# E-P-020-R1_0.net
KiCad netlist of a schematic drawn in EAGLE
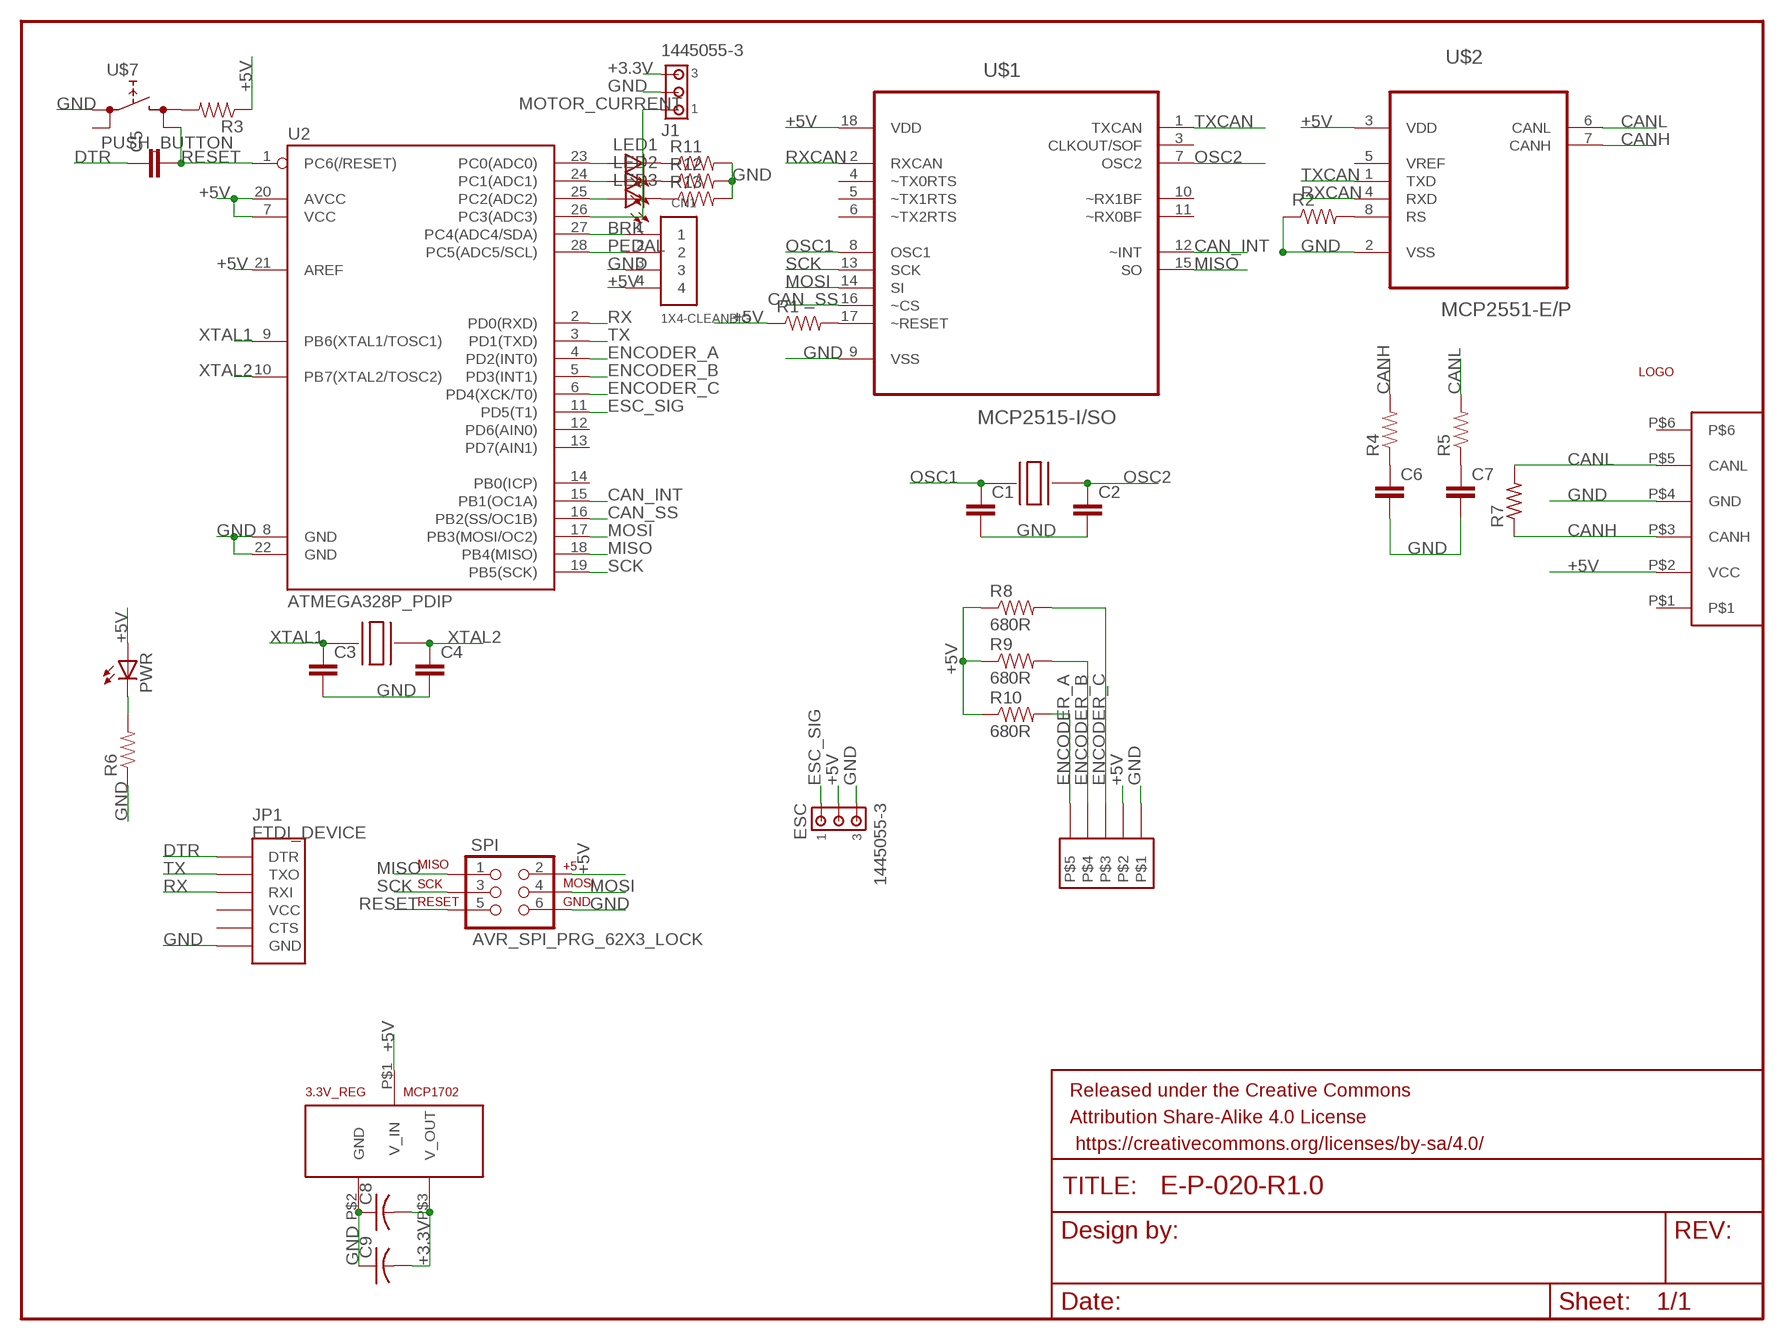
[diagram p0: schematic, sheet 1]

(export (version "E")
  (design (tool "Eeschema 10.0.6"))
  (components
    (comp (ref "3.3V_REG")
      (value "MCP1702")
      (footprint "eagle-import:SOT-23A")
      (libsource (lib "eagle-import") (part "MCP1702"))
    )
    (comp (ref "C1")
      (value "CAP0805")
      (footprint "eagle-import:0805")
      (libsource (lib "eagle-import") (part "CAP0805"))
    )
    (comp (ref "C2")
      (value "CAP0805")
      (footprint "eagle-import:0805")
      (libsource (lib "eagle-import") (part "CAP0805"))
    )
    (comp (ref "C3")
      (value "CAP0805")
      (footprint "eagle-import:0805")
      (libsource (lib "eagle-import") (part "CAP0805"))
    )
    (comp (ref "C4")
      (value "CAP0805")
      (footprint "eagle-import:0805")
      (libsource (lib "eagle-import") (part "CAP0805"))
    )
    (comp (ref "C5")
      (value "CAP0805")
      (footprint "eagle-import:0805")
      (libsource (lib "eagle-import") (part "CAP0805"))
    )
    (comp (ref "C6")
      (value "CAP0805")
      (footprint "eagle-import:0805")
      (libsource (lib "eagle-import") (part "CAP0805"))
    )
    (comp (ref "C7")
      (value "CAP0805")
      (footprint "eagle-import:0805")
      (libsource (lib "eagle-import") (part "CAP0805"))
    )
    (comp (ref "C8")
      (value "C-USC0805")
      (footprint "eagle-import:C0805")
      (libsource (lib "eagle-import") (part "C-USC0805"))
    )
    (comp (ref "C9")
      (value "C-USC0805")
      (footprint "eagle-import:C0805")
      (libsource (lib "eagle-import") (part "C-USC0805"))
    )
    (comp (ref "CAN-BUS")
      (value "CAN_6P6C")
      (footprint "eagle-import:CAN_6P6C")
      (libsource (lib "eagle-import") (part "CAN_6P6C"))
    )
    (comp (ref "CN1")
      (value "1X4-CLEANBIG")
      (footprint "eagle-import:1X04-CLEANBIG")
      (libsource (lib "eagle-import") (part "1X4-CLEANBIG"))
    )
    (comp (ref "ENCODER")
      (value "5_PIN_MICRO_MATE_N_LOCK")
      (footprint "eagle-import:5_PIN_MICRO_MATE_N_LOCK")
      (libsource (lib "eagle-import") (part "5_PIN_MICRO_MATE_N_LOCK"))
    )
    (comp (ref "ESC")
      (value "1445055-3")
      (footprint "eagle-import:1445055-3")
      (libsource (lib "eagle-import") (part "1445055-3"))
    )
    (comp (ref "FRAME1")
      (value "FRAME-LETTERNO_PACKAGE")
      (footprint "eagle-import:DUMMY")
      (fields (field (name "DESIGNER") "Nobody"))
      (libsource (lib "eagle-import") (part "FRAME-LETTERNO_PACKAGE"))
    )
    (comp (ref "J1")
      (value "1445055-3")
      (footprint "eagle-import:1445055-3")
      (libsource (lib "eagle-import") (part "1445055-3"))
    )
    (comp (ref "JP1")
      (value "FTDI_DEVICE")
      (footprint "eagle-import:FTDI_DEVICE_SIDE")
      (libsource (lib "eagle-import") (part "FTDI_DEVICE"))
    )
    (comp (ref "LED1")
      (value "LEDSMT1206")
      (footprint "eagle-import:1206")
      (libsource (lib "eagle-import") (part "adafruit_LEDSMT1206"))
    )
    (comp (ref "LED2")
      (value "LEDSMT1206")
      (footprint "eagle-import:1206")
      (libsource (lib "eagle-import") (part "adafruit_LEDSMT1206"))
    )
    (comp (ref "LED3")
      (value "LEDSMT1206")
      (footprint "eagle-import:1206")
      (libsource (lib "eagle-import") (part "adafruit_LEDSMT1206"))
    )
    (comp (ref "PWR")
      (value "LEDCHIPLED_1206")
      (footprint "eagle-import:CHIPLED_1206")
      (libsource (lib "eagle-import") (part "LEDCHIPLED_1206"))
    )
    (comp (ref "R1")
      (value "RESISTOR0805-RES")
      (footprint "eagle-import:0805")
      (libsource (lib "eagle-import") (part "SparkFun-Passives_RESISTOR0805-RES"))
    )
    (comp (ref "R2")
      (value "RESISTOR0805-RES")
      (footprint "eagle-import:0805")
      (libsource (lib "eagle-import") (part "SparkFun-Passives_RESISTOR0805-RES"))
    )
    (comp (ref "R3")
      (value "RESISTOR0805-RES")
      (footprint "eagle-import:0805")
      (libsource (lib "eagle-import") (part "SparkFun-Passives_RESISTOR0805-RES"))
    )
    (comp (ref "R4")
      (value "RESISTOR0805-RES")
      (footprint "eagle-import:0805")
      (libsource (lib "eagle-import") (part "SparkFun-Passives_RESISTOR0805-RES"))
    )
    (comp (ref "R5")
      (value "RESISTOR0805-RES")
      (footprint "eagle-import:0805")
      (libsource (lib "eagle-import") (part "SparkFun-Passives_RESISTOR0805-RES"))
    )
    (comp (ref "R6")
      (value "RESISTOR0805-RES")
      (footprint "eagle-import:0805")
      (libsource (lib "eagle-import") (part "SparkFun-Passives_RESISTOR0805-RES"))
    )
    (comp (ref "R7")
      (value "R-US_M1206")
      (footprint "eagle-import:M1206")
      (libsource (lib "eagle-import") (part "R-US_M1206"))
    )
    (comp (ref "R8")
      (value "680R")
      (footprint "eagle-import:0805")
      (libsource (lib "eagle-import") (part "0.75OHM-1/4W-1%(0805)"))
    )
    (comp (ref "R9")
      (value "680R")
      (footprint "eagle-import:0805")
      (libsource (lib "eagle-import") (part "0.75OHM-1/4W-1%(0805)"))
    )
    (comp (ref "R10")
      (value "680R")
      (footprint "eagle-import:0805")
      (libsource (lib "eagle-import") (part "0.75OHM-1/4W-1%(0805)"))
    )
    (comp (ref "R11")
      (value "RESISTOR0805-RES")
      (footprint "eagle-import:0805")
      (libsource (lib "eagle-import") (part "RESISTOR0805-RES"))
    )
    (comp (ref "R12")
      (value "RESISTOR0805-RES")
      (footprint "eagle-import:0805")
      (libsource (lib "eagle-import") (part "RESISTOR0805-RES"))
    )
    (comp (ref "R13")
      (value "RESISTOR0805-RES")
      (footprint "eagle-import:0805")
      (libsource (lib "eagle-import") (part "RESISTOR0805-RES"))
    )
    (comp (ref "SPI")
      (value "AVR_SPI_PRG_62X3_LOCK")
      (footprint "eagle-import:2X3_LOCK")
      (libsource (lib "eagle-import") (part "AVR_SPI_PRG_62X3_LOCK"))
    )
    (comp (ref "U$1")
      (value "MCP2515-I/SO")
      (footprint "eagle-import:SOIC127P1034X264-18N")
      (libsource (lib "eagle-import") (part "MCP2515-I/SO"))
    )
    (comp (ref "U$2")
      (value "MCP2551-E/P")
      (footprint "eagle-import:DIP254P762X432-8")
      (libsource (lib "eagle-import") (part "MCP2551-E/P"))
    )
    (comp (ref "U$3")
      (value "CRYSTAL")
      (footprint "eagle-import:7A_CRYSTAL")
      (libsource (lib "eagle-import") (part "CRYSTAL"))
    )
    (comp (ref "U$4")
      (value "CRYSTAL")
      (footprint "eagle-import:7A_CRYSTAL")
      (libsource (lib "eagle-import") (part "CRYSTAL"))
    )
    (comp (ref "U$6")
      (value "LOGO")
      (footprint "eagle-import:LOGO")
      (libsource (lib "eagle-import") (part "LOGO"))
    )
    (comp (ref "U$7")
      (value "PUSH_BUTTON")
      (footprint "eagle-import:PUSHBUTTON")
      (libsource (lib "eagle-import") (part "PUSH_BUTTON"))
    )
    (comp (ref "U2")
      (value "ATMEGA328P_PDIP")
      (footprint "eagle-import:DIL28-3")
      (libsource (lib "eagle-import") (part "ATMEGA328P_PDIP"))
    )
  )
  (nets
    (net (code "1") (name "/+3.3V") (class "Default")
      (node (ref "3.3V_REG") (pin "P$3") (pinfunction "V_OUT_P$3") (pintype "bidirectional"))
      (node (ref "C8") (pin "2") (pinfunction "2_2") (pintype "passive"))
      (node (ref "C9") (pin "2") (pinfunction "2_2") (pintype "passive"))
      (node (ref "J1") (pin "3") (pinfunction "3_3") (pintype "passive"))
    )
    (net (code "2") (name "/+5V") (class "Default")
      (node (ref "3.3V_REG") (pin "P$1") (pinfunction "V_IN_P$1") (pintype "bidirectional"))
      (node (ref "CAN-BUS") (pin "P$2") (pinfunction "VCC_P$2") (pintype "bidirectional"))
      (node (ref "CN1") (pin "4") (pinfunction "4_4") (pintype "bidirectional"))
      (node (ref "ENCODER") (pin "P$4") (pinfunction "P$2_P$4") (pintype "bidirectional"))
      (node (ref "ESC") (pin "2") (pinfunction "2_2") (pintype "passive"))
      (node (ref "PWR") (pin "A") (pinfunction "A_A") (pintype "passive"))
      (node (ref "R1") (pin "1") (pinfunction "1_1") (pintype "passive"))
      (node (ref "R10") (pin "1") (pinfunction "1_1") (pintype "passive"))
      (node (ref "R3") (pin "1") (pinfunction "1_1") (pintype "passive"))
      (node (ref "R8") (pin "1") (pinfunction "1_1") (pintype "passive"))
      (node (ref "R9") (pin "1") (pinfunction "1_1") (pintype "passive"))
      (node (ref "SPI") (pin "2") (pinfunction "2_2") (pintype "passive"))
      (node (ref "U$1") (pin "18") (pinfunction "VDD_18") (pintype "power_in"))
      (node (ref "U$2") (pin "3") (pinfunction "VDD_3") (pintype "power_in"))
      (node (ref "U2") (pin "20") (pinfunction "AVCC_20") (pintype "bidirectional"))
      (node (ref "U2") (pin "21") (pinfunction "AREF_21") (pintype "bidirectional"))
      (node (ref "U2") (pin "7") (pinfunction "VCC_7") (pintype "bidirectional"))
    )
    (net (code "3") (name "/BRK") (class "Default")
      (node (ref "CN1") (pin "1") (pinfunction "1_1") (pintype "bidirectional"))
      (node (ref "U2") (pin "27") (pinfunction "PC4(ADC4/SDA)_27") (pintype "bidirectional"))
    )
    (net (code "4") (name "/CANH") (class "Default")
      (node (ref "CAN-BUS") (pin "P$3") (pinfunction "CANH_P$3") (pintype "bidirectional"))
      (node (ref "R4") (pin "2") (pinfunction "2_2") (pintype "passive"))
      (node (ref "R7") (pin "1") (pinfunction "1_1") (pintype "passive"))
      (node (ref "U$2") (pin "7") (pinfunction "CANH_7") (pintype "output"))
    )
    (net (code "5") (name "/CANL") (class "Default")
      (node (ref "CAN-BUS") (pin "P$5") (pinfunction "CANL_P$5") (pintype "bidirectional"))
      (node (ref "R5") (pin "2") (pinfunction "2_2") (pintype "passive"))
      (node (ref "R7") (pin "2") (pinfunction "2_2") (pintype "passive"))
      (node (ref "U$2") (pin "6") (pinfunction "CANL_6") (pintype "output"))
    )
    (net (code "6") (name "/CAN_INT") (class "Default")
      (node (ref "U$1") (pin "12") (pinfunction "~{INT}_12") (pintype "output"))
      (node (ref "U2") (pin "15") (pinfunction "PB1(OC1A)_15") (pintype "bidirectional"))
    )
    (net (code "7") (name "/CAN_SS") (class "Default")
      (node (ref "U$1") (pin "16") (pinfunction "~{CS}_16") (pintype "input"))
      (node (ref "U2") (pin "16") (pinfunction "PB2(SS/OC1B)_16") (pintype "bidirectional"))
    )
    (net (code "8") (name "/DTR") (class "Default")
      (node (ref "C5") (pin "1") (pinfunction "1_1") (pintype "passive"))
      (node (ref "JP1") (pin "P$1") (pinfunction "DTR_P$1") (pintype "bidirectional"))
    )
    (net (code "9") (name "/ENCODER_A") (class "Default")
      (node (ref "ENCODER") (pin "P$1") (pinfunction "P$5_P$1") (pintype "bidirectional"))
      (node (ref "R10") (pin "2") (pinfunction "2_2") (pintype "passive"))
      (node (ref "U2") (pin "4") (pinfunction "PD2(INT0)_4") (pintype "bidirectional"))
    )
    (net (code "10") (name "/ENCODER_B") (class "Default")
      (node (ref "ENCODER") (pin "P$2") (pinfunction "P$4_P$2") (pintype "bidirectional"))
      (node (ref "R9") (pin "2") (pinfunction "2_2") (pintype "passive"))
      (node (ref "U2") (pin "5") (pinfunction "PD3(INT1)_5") (pintype "bidirectional"))
    )
    (net (code "11") (name "/ENCODER_C") (class "Default")
      (node (ref "ENCODER") (pin "P$3") (pinfunction "P$3_P$3") (pintype "bidirectional"))
      (node (ref "R8") (pin "2") (pinfunction "2_2") (pintype "passive"))
      (node (ref "U2") (pin "6") (pinfunction "PD4(XCK/T0)_6") (pintype "bidirectional"))
    )
    (net (code "12") (name "/ESC_SIG") (class "Default")
      (node (ref "ESC") (pin "1") (pinfunction "1_1") (pintype "passive"))
      (node (ref "U2") (pin "11") (pinfunction "PD5(T1)_11") (pintype "bidirectional"))
    )
    (net (code "13") (name "/GND") (class "Default")
      (node (ref "3.3V_REG") (pin "P$2") (pinfunction "GND_P$2") (pintype "bidirectional"))
      (node (ref "C1") (pin "2") (pinfunction "2_2") (pintype "passive"))
      (node (ref "C2") (pin "2") (pinfunction "2_2") (pintype "passive"))
      (node (ref "C3") (pin "2") (pinfunction "2_2") (pintype "passive"))
      (node (ref "C4") (pin "2") (pinfunction "2_2") (pintype "passive"))
      (node (ref "C6") (pin "2") (pinfunction "2_2") (pintype "passive"))
      (node (ref "C7") (pin "2") (pinfunction "2_2") (pintype "passive"))
      (node (ref "C8") (pin "1") (pinfunction "1_1") (pintype "passive"))
      (node (ref "C9") (pin "1") (pinfunction "1_1") (pintype "passive"))
      (node (ref "CAN-BUS") (pin "P$4") (pinfunction "GND_P$4") (pintype "bidirectional"))
      (node (ref "CN1") (pin "3") (pinfunction "3_3") (pintype "bidirectional"))
      (node (ref "ENCODER") (pin "P$5") (pinfunction "P$1_P$5") (pintype "bidirectional"))
      (node (ref "ESC") (pin "3") (pinfunction "3_3") (pintype "passive"))
      (node (ref "J1") (pin "2") (pinfunction "2_2") (pintype "passive"))
      (node (ref "JP1") (pin "P$6") (pinfunction "GND_P$6") (pintype "bidirectional"))
      (node (ref "R11") (pin "2") (pinfunction "2_2") (pintype "passive"))
      (node (ref "R12") (pin "2") (pinfunction "2_2") (pintype "passive"))
      (node (ref "R13") (pin "2") (pinfunction "2_2") (pintype "passive"))
      (node (ref "R2") (pin "1") (pinfunction "1_1") (pintype "passive"))
      (node (ref "R6") (pin "1") (pinfunction "1_1") (pintype "passive"))
      (node (ref "SPI") (pin "6") (pinfunction "6_6") (pintype "passive"))
      (node (ref "U$1") (pin "9") (pinfunction "VSS_9") (pintype "power_in"))
      (node (ref "U$2") (pin "2") (pinfunction "VSS_2") (pintype "passive"))
      (node (ref "U$7") (pin "L1") (pinfunction "L_L1") (pintype "passive"))
      (node (ref "U2") (pin "22") (pinfunction "GND_22") (pintype "bidirectional"))
      (node (ref "U2") (pin "8") (pinfunction "GND_8") (pintype "bidirectional"))
    )
    (net (code "14") (name "/MISO") (class "Default")
      (node (ref "SPI") (pin "1") (pinfunction "1_1") (pintype "passive"))
      (node (ref "U$1") (pin "15") (pinfunction "SO_15") (pintype "output"))
      (node (ref "U2") (pin "18") (pinfunction "PB4(MISO)_18") (pintype "bidirectional"))
    )
    (net (code "15") (name "/MOSI") (class "Default")
      (node (ref "SPI") (pin "4") (pinfunction "4_4") (pintype "passive"))
      (node (ref "U$1") (pin "14") (pinfunction "SI_14") (pintype "input"))
      (node (ref "U2") (pin "17") (pinfunction "PB3(MOSI/OC2)_17") (pintype "bidirectional"))
    )
    (net (code "16") (name "/MOTOR_CURRENT") (class "Default")
      (node (ref "J1") (pin "1") (pinfunction "1_1") (pintype "passive"))
      (node (ref "U2") (pin "26") (pinfunction "PC3(ADC3)_26") (pintype "bidirectional"))
    )
    (net (code "17") (name "/OSC1") (class "Default")
      (node (ref "C1") (pin "1") (pinfunction "1_1") (pintype "passive"))
      (node (ref "U$1") (pin "8") (pinfunction "OSC1_8") (pintype "input"))
      (node (ref "U$3") (pin "P$2") (pinfunction "P$2_P$2") (pintype "bidirectional"))
    )
    (net (code "18") (name "/OSC2") (class "Default")
      (node (ref "C2") (pin "1") (pinfunction "1_1") (pintype "passive"))
      (node (ref "U$1") (pin "7") (pinfunction "OSC2_7") (pintype "output"))
      (node (ref "U$3") (pin "P$1") (pinfunction "P$1_P$1") (pintype "bidirectional"))
    )
    (net (code "19") (name "/PEDAL") (class "Default")
      (node (ref "CN1") (pin "2") (pinfunction "2_2") (pintype "bidirectional"))
      (node (ref "U2") (pin "28") (pinfunction "PC5(ADC5/SCL)_28") (pintype "bidirectional"))
    )
    (net (code "20") (name "/RESET") (class "Default")
      (node (ref "C5") (pin "2") (pinfunction "2_2") (pintype "passive"))
      (node (ref "SPI") (pin "5") (pinfunction "5_5") (pintype "passive"))
      (node (ref "U$7") (pin "R2") (pinfunction "R_R2") (pintype "passive"))
      (node (ref "U2") (pin "1") (pinfunction "PC6(/RESET)_1") (pintype "bidirectional"))
    )
    (net (code "21") (name "/RX") (class "Default")
      (node (ref "JP1") (pin "P$3") (pinfunction "RXI_P$3") (pintype "bidirectional"))
      (node (ref "U2") (pin "2") (pinfunction "PD0(RXD)_2") (pintype "bidirectional"))
    )
    (net (code "22") (name "/RXCAN") (class "Default")
      (node (ref "U$1") (pin "2") (pinfunction "RXCAN_2") (pintype "input"))
      (node (ref "U$2") (pin "4") (pinfunction "RXD_4") (pintype "input"))
    )
    (net (code "23") (name "/SCK") (class "Default")
      (node (ref "SPI") (pin "3") (pinfunction "3_3") (pintype "passive"))
      (node (ref "U$1") (pin "13") (pinfunction "SCK_13") (pintype "input"))
      (node (ref "U2") (pin "19") (pinfunction "PB5(SCK)_19") (pintype "bidirectional"))
    )
    (net (code "24") (name "/TX") (class "Default")
      (node (ref "JP1") (pin "P$2") (pinfunction "TXO_P$2") (pintype "bidirectional"))
      (node (ref "U2") (pin "3") (pinfunction "PD1(TXD)_3") (pintype "bidirectional"))
    )
    (net (code "25") (name "/TXCAN") (class "Default")
      (node (ref "U$1") (pin "1") (pinfunction "TXCAN_1") (pintype "output"))
      (node (ref "U$2") (pin "1") (pinfunction "TXD_1") (pintype "input"))
    )
    (net (code "26") (name "/XTAL1") (class "Default")
      (node (ref "C3") (pin "1") (pinfunction "1_1") (pintype "passive"))
      (node (ref "U$4") (pin "P$2") (pinfunction "P$2_P$2") (pintype "bidirectional"))
      (node (ref "U2") (pin "9") (pinfunction "PB6(XTAL1/TOSC1)_9") (pintype "bidirectional"))
    )
    (net (code "27") (name "/XTAL2") (class "Default")
      (node (ref "C4") (pin "1") (pinfunction "1_1") (pintype "passive"))
      (node (ref "U$4") (pin "P$1") (pinfunction "P$1_P$1") (pintype "bidirectional"))
      (node (ref "U2") (pin "10") (pinfunction "PB7(XTAL2/TOSC2)_10") (pintype "bidirectional"))
    )
    (net (code "28") (name "Net-(C6-Pad1)") (class "Default")
      (node (ref "C6") (pin "1") (pinfunction "1_1") (pintype "passive"))
      (node (ref "R4") (pin "1") (pinfunction "1_1") (pintype "passive"))
    )
    (net (code "29") (name "Net-(C7-Pad1)") (class "Default")
      (node (ref "C7") (pin "1") (pinfunction "1_1") (pintype "passive"))
      (node (ref "R5") (pin "1") (pinfunction "1_1") (pintype "passive"))
    )
    (net (code "30") (name "Net-(LED1-PadC)") (class "Default")
      (node (ref "LED1") (pin "C") (pinfunction "C_C") (pintype "passive"))
      (node (ref "R11") (pin "1") (pinfunction "1_1") (pintype "passive"))
    )
    (net (code "31") (name "Net-(LED2-PadC)") (class "Default")
      (node (ref "LED2") (pin "C") (pinfunction "C_C") (pintype "passive"))
      (node (ref "R12") (pin "1") (pinfunction "1_1") (pintype "passive"))
    )
    (net (code "32") (name "Net-(LED3-PadC)") (class "Default")
      (node (ref "LED3") (pin "C") (pinfunction "C_C") (pintype "passive"))
      (node (ref "R13") (pin "1") (pinfunction "1_1") (pintype "passive"))
    )
    (net (code "33") (name "Net-(PWR-PadC)") (class "Default")
      (node (ref "PWR") (pin "C") (pinfunction "C_C") (pintype "passive"))
      (node (ref "R6") (pin "2") (pinfunction "2_2") (pintype "passive"))
    )
    (net (code "34") (name "Net-(R3-Pad2)") (class "Default")
      (node (ref "R3") (pin "2") (pinfunction "2_2") (pintype "passive"))
      (node (ref "U$7") (pin "R1") (pinfunction "R_R1") (pintype "passive"))
    )
    (net (code "35") (name "Net-(U$1-~{RESET})") (class "Default")
      (node (ref "R1") (pin "2") (pinfunction "2_2") (pintype "passive"))
      (node (ref "U$1") (pin "17") (pinfunction "~{RESET}_17") (pintype "input"))
    )
    (net (code "36") (name "Net-(U$2-RS)") (class "Default")
      (node (ref "R2") (pin "2") (pinfunction "2_2") (pintype "passive"))
      (node (ref "U$2") (pin "8") (pinfunction "RS_8") (pintype "input"))
    )
    (net (code "37") (name "Net-(U2-PC0(ADC0))") (class "Default")
      (node (ref "LED1") (pin "A") (pinfunction "A_A") (pintype "passive"))
      (node (ref "U2") (pin "23") (pinfunction "PC0(ADC0)_23") (pintype "bidirectional"))
    )
    (net (code "38") (name "Net-(U2-PC1(ADC1))") (class "Default")
      (node (ref "LED2") (pin "A") (pinfunction "A_A") (pintype "passive"))
      (node (ref "U2") (pin "24") (pinfunction "PC1(ADC1)_24") (pintype "bidirectional"))
    )
    (net (code "39") (name "Net-(U2-PC2(ADC2))") (class "Default")
      (node (ref "LED3") (pin "A") (pinfunction "A_A") (pintype "passive"))
      (node (ref "U2") (pin "25") (pinfunction "PC2(ADC2)_25") (pintype "bidirectional"))
    )
    (net (code "40") (name "unconnected-(CAN-BUS-PadP$1)") (class "Default")
      (node (ref "CAN-BUS") (pin "P$1") (pinfunction "P$1_P$1") (pintype "bidirectional"))
    )
    (net (code "41") (name "unconnected-(CAN-BUS-PadP$6)") (class "Default")
      (node (ref "CAN-BUS") (pin "P$6") (pinfunction "P$6_P$6") (pintype "bidirectional"))
    )
    (net (code "42") (name "unconnected-(JP1-CTS-PadP$5)") (class "Default")
      (node (ref "JP1") (pin "P$5") (pinfunction "CTS_P$5") (pintype "bidirectional"))
    )
    (net (code "43") (name "unconnected-(JP1-VCC-PadP$4)") (class "Default")
      (node (ref "JP1") (pin "P$4") (pinfunction "VCC_P$4") (pintype "bidirectional"))
    )
    (net (code "44") (name "unconnected-(U$1-CLKOUT{slash}SOF-Pad3)") (class "Default")
      (node (ref "U$1") (pin "3") (pinfunction "CLKOUT/SOF_3") (pintype "output"))
    )
    (net (code "45") (name "unconnected-(U$1-~{RX0BF}-Pad11)") (class "Default")
      (node (ref "U$1") (pin "11") (pinfunction "~{RX0BF}_11") (pintype "output"))
    )
    (net (code "46") (name "unconnected-(U$1-~{RX1BF}-Pad10)") (class "Default")
      (node (ref "U$1") (pin "10") (pinfunction "~{RX1BF}_10") (pintype "output"))
    )
    (net (code "47") (name "unconnected-(U$1-~{TX0RTS}-Pad4)") (class "Default")
      (node (ref "U$1") (pin "4") (pinfunction "~{TX0RTS}_4") (pintype "input"))
    )
    (net (code "48") (name "unconnected-(U$1-~{TX1RTS}-Pad5)") (class "Default")
      (node (ref "U$1") (pin "5") (pinfunction "~{TX1RTS}_5") (pintype "input"))
    )
    (net (code "49") (name "unconnected-(U$1-~{TX2RTS}-Pad6)") (class "Default")
      (node (ref "U$1") (pin "6") (pinfunction "~{TX2RTS}_6") (pintype "input"))
    )
    (net (code "50") (name "unconnected-(U$2-VREF-Pad5)") (class "Default")
      (node (ref "U$2") (pin "5") (pinfunction "VREF_5") (pintype "input"))
    )
    (net (code "51") (name "unconnected-(U$7-L-PadL2)") (class "Default")
      (node (ref "U$7") (pin "L2") (pinfunction "L_L2") (pintype "passive"))
    )
    (net (code "52") (name "unconnected-(U2-PB0(ICP)-Pad14)") (class "Default")
      (node (ref "U2") (pin "14") (pinfunction "PB0(ICP)_14") (pintype "bidirectional"))
    )
    (net (code "53") (name "unconnected-(U2-PD6(AIN0)-Pad12)") (class "Default")
      (node (ref "U2") (pin "12") (pinfunction "PD6(AIN0)_12") (pintype "bidirectional"))
    )
    (net (code "54") (name "unconnected-(U2-PD7(AIN1)-Pad13)") (class "Default")
      (node (ref "U2") (pin "13") (pinfunction "PD7(AIN1)_13") (pintype "bidirectional"))
    )
  )
)
